# bathroom_fan_power_supply.net
KiCad netlist of a schematic drawn in EAGLE
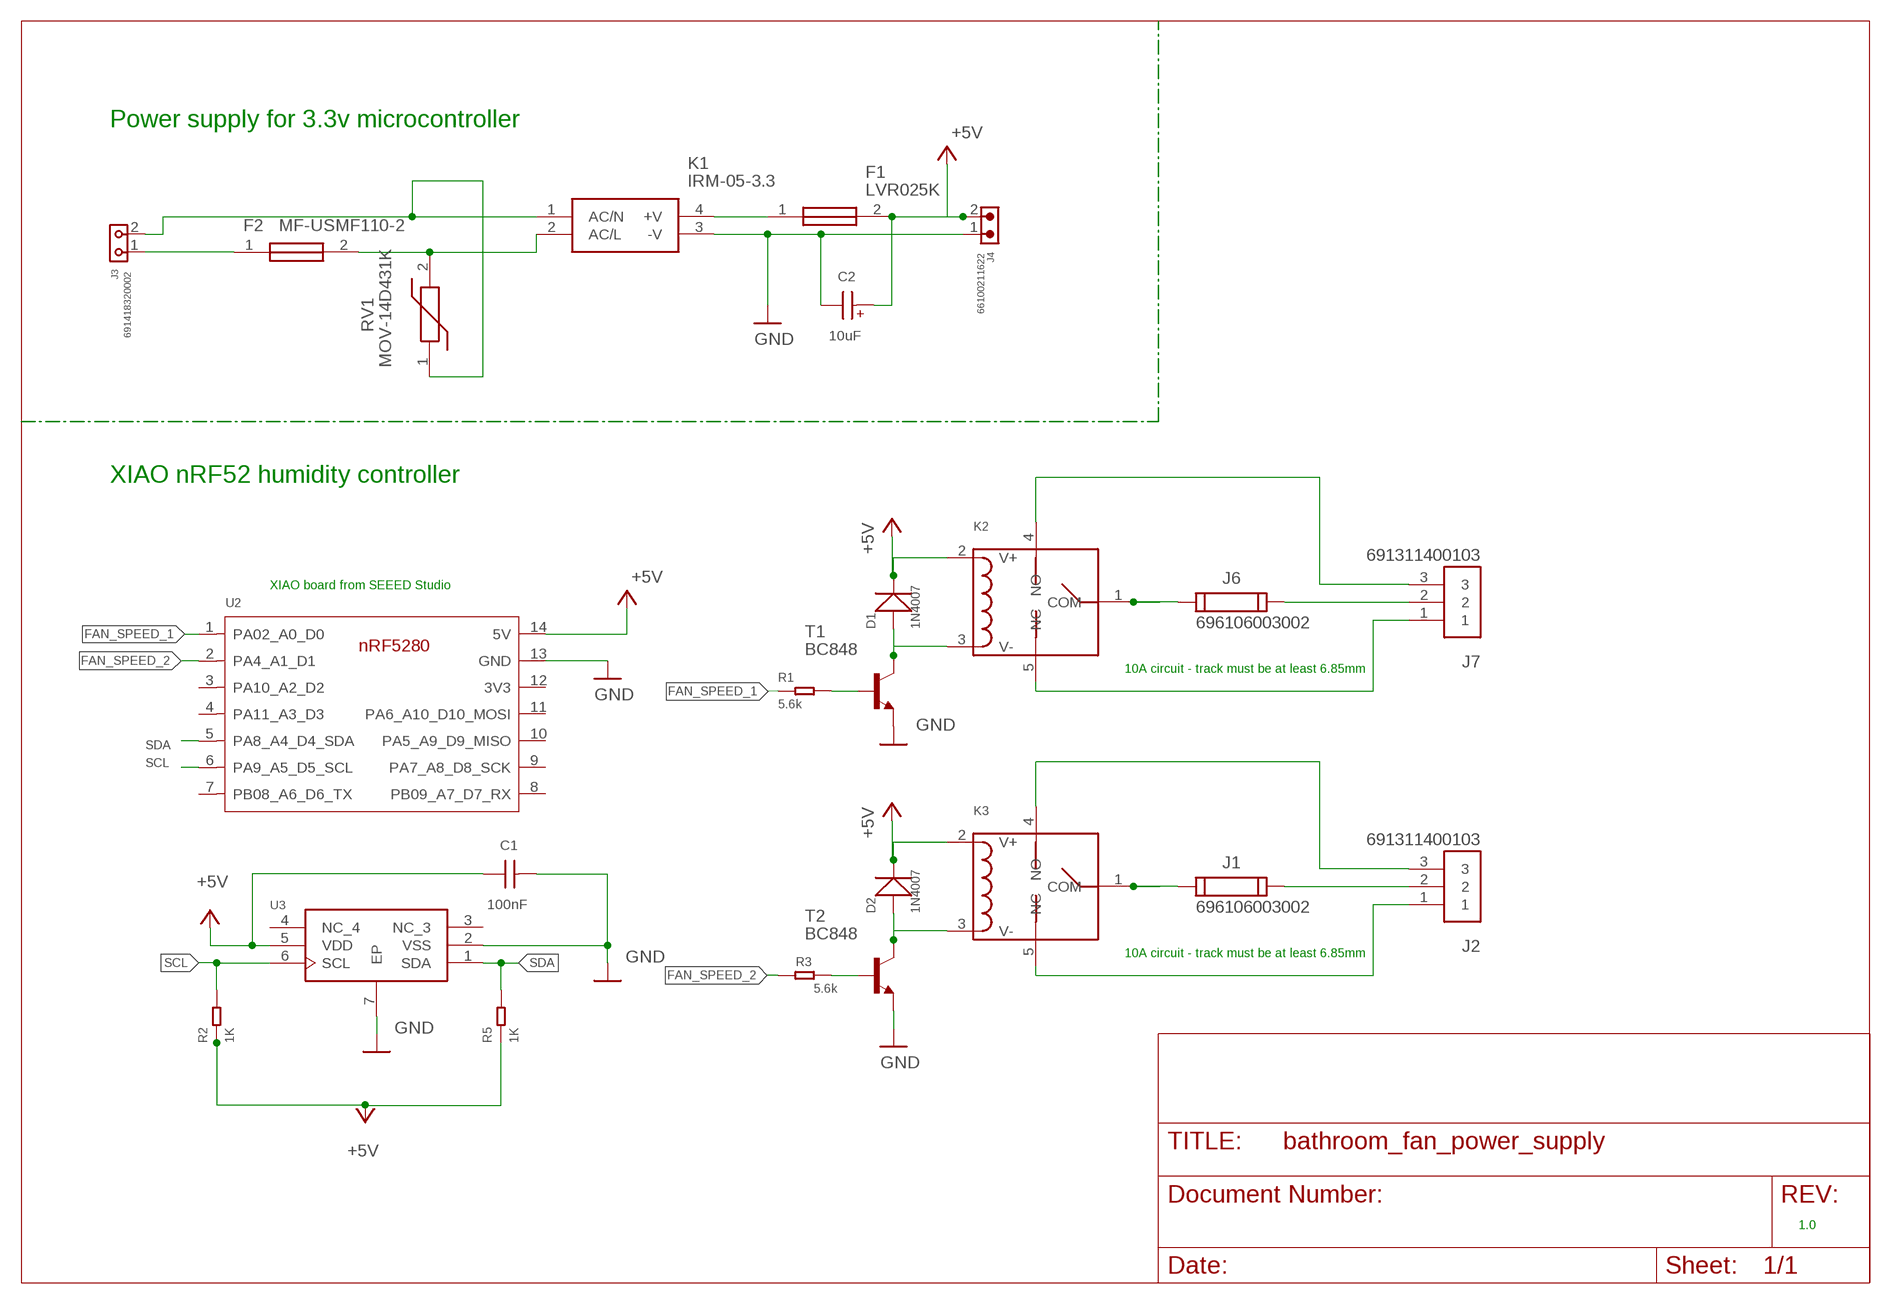
[diagram p0: schematic, sheet 1]

(export (version "E")
  (design (tool "Eeschema 10.0.6"))
  (components
    (comp (ref "C1")
      (value "100nF")
      (footprint "eagle-import:WCAP-CSGP_0805_H0.8_R")
      (libsource (lib "eagle-import") (part "WCAP-CSGP_0805_H0.8_10V(DC)_R_885012207016"))
    )
    (comp (ref "C2")
      (value "10uF")
      (footprint "eagle-import:WCAP-AS5H_4X5.5(DXL)")
      (libsource (lib "eagle-import") (part "WCAP-AS5H_4X5.5_865230340001"))
    )
    (comp (ref "D1")
      (value "1N4007")
      (footprint "eagle-import:DO-214AC")
      (libsource (lib "eagle-import") (part "DIODE-GEN-PURPOSE-1KV-1A(DO-214AC)"))
    )
    (comp (ref "D2")
      (value "1N4007")
      (footprint "eagle-import:DO-214AC")
      (libsource (lib "eagle-import") (part "DIODE-GEN-PURPOSE-1KV-1A(DO-214AC)"))
    )
    (comp (ref "F1")
      (value "LVR025K")
      (footprint "eagle-import:LVR025K")
      (fields (field (name "MOUSER_PART_NUMBER") "650-LVR025K"))
      (libsource (lib "eagle-import") (part "LVR025K"))
    )
    (comp (ref "F2")
      (value "MF-USMF110-2")
      (footprint "eagle-import:FUSC3226X85N")
      (fields (field (name "MOUSER_PART_NUMBER") "652-MF-USMF110-2"))
      (libsource (lib "eagle-import") (part "MF-USMF110-2"))
    )
    (comp (ref "J1")
      (value "696106003002")
      (footprint "eagle-import:696106003002")
      (libsource (lib "eagle-import") (part "696106003002"))
    )
    (comp (ref "J2")
      (value "691311400103")
      (footprint "eagle-import:TERMINALBLOCK_PLUGGABLE-3-7.62MM")
      (fields
        (field (name "DIGIKEY_PART_NO") "732-2824-ND")
        (field (name "MANUFACTURER") "WURTH ELEKTRONIK")
        (field (name "CREATED_BY") "PCBLayout.com")
      )
      (libsource (lib "eagle-import") (part "691311400103"))
    )
    (comp (ref "J3")
      (value "691418320002")
      (footprint "eagle-import:691418320002")
      (libsource (lib "eagle-import") (part "691418320002"))
    )
    (comp (ref "J4")
      (value "66100211622")
      (footprint "eagle-import:66100211622")
      (libsource (lib "eagle-import") (part "66100211622"))
    )
    (comp (ref "J6")
      (value "696106003002")
      (footprint "eagle-import:696106003002")
      (libsource (lib "eagle-import") (part "696106003002"))
    )
    (comp (ref "J7")
      (value "691311400103")
      (footprint "eagle-import:TERMINALBLOCK_PLUGGABLE-3-7.62MM")
      (fields
        (field (name "DIGIKEY_PART_NO") "732-2824-ND")
        (field (name "MANUFACTURER") "WURTH ELEKTRONIK")
        (field (name "CREATED_BY") "PCBLayout.com")
      )
      (libsource (lib "eagle-import") (part "691311400103"))
    )
    (comp (ref "K1")
      (value "IRM-05-3.3")
      (footprint "eagle-import:IRM-05-3.3_1")
      (fields (field (name "MOUSER_PART_NUMBER") "709-IRM05-3.3"))
      (libsource (lib "eagle-import") (part "IRM-05-3.3"))
    )
    (comp (ref "K2")
      (value "HLS8L-DC3V-S-C")
      (footprint "eagle-import:REY5-19.0X15.0X15.0MM")
      (libsource (lib "eagle-import") (part "RELAY-HLS8L-DC5V-S-CHLS8L-DC5V-S-C"))
    )
    (comp (ref "K3")
      (value "HLS8L-DC3V-S-C")
      (footprint "eagle-import:REY5-19.0X15.0X15.0MM")
      (libsource (lib "eagle-import") (part "RELAY-HLS8L-DC5V-S-CHLS8L-DC5V-S-C"))
    )
    (comp (ref "R1")
      (value "5.6k")
      (footprint "eagle-import:R0805")
      (fields (field (name "MPN") "RC0805JR-071KL"))
      (libsource (lib "eagle-import") (part "SMD-RES-5.6K-5%-1/8W(0805)"))
    )
    (comp (ref "R2")
      (value "1K")
      (footprint "eagle-import:R0805")
      (fields (field (name "MPN") "RC0805JR-071KL"))
      (libsource (lib "eagle-import") (part "SMD-RES-5.6K-5%-1/8W(0805)"))
    )
    (comp (ref "R3")
      (value "5.6k")
      (footprint "eagle-import:R0805")
      (fields (field (name "MPN") "RC0805JR-071KL"))
      (libsource (lib "eagle-import") (part "SMD-RES-5.6K-5%-1/8W(0805)"))
    )
    (comp (ref "R5")
      (value "1K")
      (footprint "eagle-import:R0805")
      (fields (field (name "MPN") "RC0805JR-071KL"))
      (libsource (lib "eagle-import") (part "SMD-RES-5.6K-5%-1/8W(0805)"))
    )
    (comp (ref "RV1")
      (value "MOV-14D431K")
      (footprint "eagle-import:MOV-14D(5.2MM-T)")
      (fields (field (name "MOUSER_PART_NUMBER") "652-MOV-14D431K"))
      (libsource (lib "eagle-import") (part "MOV-14D431K"))
    )
    (comp (ref "T1")
      (value "BC848")
      (footprint "eagle-import:SOT23")
      (libsource (lib "eagle-import") (part "BC848"))
    )
    (comp (ref "T2")
      (value "BC848")
      (footprint "eagle-import:SOT23")
      (libsource (lib "eagle-import") (part "BC848"))
    )
    (comp (ref "U2")
      (value "MOUDLE-SEEEDUINO-XIAO")
      (footprint "eagle-import:MOUDLE14P-2.54-21X17.8MM")
      (libsource (lib "eagle-import") (part "MOUDLE-SEEEDUINO-XIAO"))
    )
    (comp (ref "U3")
      (value "SHT21")
      (footprint "eagle-import:6-TDFN")
      (fields
        (field (name "DIGIKEY_PART_NUMBER") "1649-1005-1-ND")
        (field (name "MANUFACTURER") "Sensirion AG")
        (field (name "CREATED_BY") "PCBLayout.com")
      )
      (libsource (lib "eagle-import") (part "SHT21"))
    )
  )
  (nets
    (net (code "1") (name "+5V") (class "Default")
      (node (ref "C1") (pin "1") (pinfunction "1_1") (pintype "passive"))
      (node (ref "C2") (pin "1") (pinfunction "+_1") (pintype "passive"))
      (node (ref "D1") (pin "2") (pinfunction "-_2") (pintype "passive"))
      (node (ref "D2") (pin "2") (pinfunction "-_2") (pintype "passive"))
      (node (ref "F1") (pin "2") (pinfunction "2_2") (pintype "bidirectional"))
      (node (ref "J4") (pin "2") (pinfunction "2_2") (pintype "passive"))
      (node (ref "K2") (pin "2") (pinfunction "V+_2") (pintype "bidirectional"))
      (node (ref "K3") (pin "2") (pinfunction "V+_2") (pintype "bidirectional"))
      (node (ref "R2") (pin "1") (pinfunction "1_1") (pintype "passive"))
      (node (ref "R5") (pin "1") (pinfunction "1_1") (pintype "passive"))
      (node (ref "U2") (pin "14") (pinfunction "5V_14") (pintype "bidirectional"))
      (node (ref "U3") (pin "5") (pinfunction "VDD_5") (pintype "power_in"))
    )
    (net (code "2") (name "FAN_SPEED_1") (class "Default")
      (node (ref "R1") (pin "1") (pinfunction "1_1") (pintype "passive"))
      (node (ref "U2") (pin "1") (pinfunction "PA02_A0_D0_1") (pintype "bidirectional"))
    )
    (net (code "3") (name "FAN_SPEED_2") (class "Default")
      (node (ref "R3") (pin "1") (pinfunction "1_1") (pintype "passive"))
      (node (ref "U2") (pin "2") (pinfunction "PA4_A1_D1_2") (pintype "bidirectional"))
    )
    (net (code "4") (name "GND") (class "Default")
      (node (ref "C1") (pin "2") (pinfunction "2_2") (pintype "passive"))
      (node (ref "C2") (pin "2") (pinfunction "-_2") (pintype "passive"))
      (node (ref "J4") (pin "1") (pinfunction "1_1") (pintype "passive"))
      (node (ref "K1") (pin "3") (pinfunction "-V_3") (pintype "bidirectional"))
      (node (ref "T1") (pin "2") (pinfunction "E_2") (pintype "passive"))
      (node (ref "T2") (pin "2") (pinfunction "E_2") (pintype "passive"))
      (node (ref "U2") (pin "13") (pinfunction "GND_13") (pintype "bidirectional"))
      (node (ref "U3") (pin "2") (pinfunction "VSS_2") (pintype "power_in"))
      (node (ref "U3") (pin "7") (pinfunction "EP_7") (pintype "power_in"))
    )
    (net (code "5") (name "Net-(D1-+)") (class "Default")
      (node (ref "D1") (pin "1") (pinfunction "+_1") (pintype "passive"))
      (node (ref "K2") (pin "3") (pinfunction "V-_3") (pintype "bidirectional"))
      (node (ref "T1") (pin "3") (pinfunction "C_3") (pintype "passive"))
    )
    (net (code "6") (name "Net-(D2-+)") (class "Default")
      (node (ref "D2") (pin "1") (pinfunction "+_1") (pintype "passive"))
      (node (ref "K3") (pin "3") (pinfunction "V-_3") (pintype "bidirectional"))
      (node (ref "T2") (pin "3") (pinfunction "C_3") (pintype "passive"))
    )
    (net (code "7") (name "Net-(F2-Pad1)") (class "Default")
      (node (ref "F2") (pin "1") (pinfunction "1_1") (pintype "bidirectional"))
      (node (ref "J3") (pin "1") (pinfunction "1_1") (pintype "passive"))
    )
    (net (code "8") (name "Net-(J1-Pad2)") (class "Default")
      (node (ref "J1") (pin "2") (pinfunction "2_2") (pintype "passive"))
      (node (ref "J2") (pin "2") (pinfunction "2_2") (pintype "passive"))
    )
    (net (code "9") (name "Net-(J6-Pad2)") (class "Default")
      (node (ref "J6") (pin "2") (pinfunction "2_2") (pintype "passive"))
      (node (ref "J7") (pin "2") (pinfunction "2_2") (pintype "passive"))
    )
    (net (code "10") (name "Net-(K1-+V)") (class "Default")
      (node (ref "F1") (pin "1") (pinfunction "1_1") (pintype "bidirectional"))
      (node (ref "K1") (pin "4") (pinfunction "+V_4") (pintype "bidirectional"))
    )
    (net (code "11") (name "Net-(K1-AC{slash}L)") (class "Default")
      (node (ref "F2") (pin "2") (pinfunction "2_2") (pintype "bidirectional"))
      (node (ref "K1") (pin "2") (pinfunction "AC/L_2") (pintype "bidirectional"))
      (node (ref "RV1") (pin "2") (pinfunction "2_2") (pintype "bidirectional"))
    )
    (net (code "12") (name "Net-(K1-AC{slash}N)") (class "Default")
      (node (ref "J3") (pin "2") (pinfunction "2_2") (pintype "passive"))
      (node (ref "K1") (pin "1") (pinfunction "AC/N_1") (pintype "bidirectional"))
      (node (ref "RV1") (pin "1") (pinfunction "1_1") (pintype "bidirectional"))
    )
    (net (code "13") (name "Net-(K2-COM)") (class "Default")
      (node (ref "J6") (pin "1") (pinfunction "1_1") (pintype "passive"))
      (node (ref "K2") (pin "1") (pinfunction "COM_1") (pintype "bidirectional"))
    )
    (net (code "14") (name "Net-(K2-NC)") (class "Default")
      (node (ref "J7") (pin "1") (pinfunction "1_1") (pintype "passive"))
      (node (ref "K2") (pin "5") (pinfunction "NC_5") (pintype "bidirectional"))
    )
    (net (code "15") (name "Net-(K2-NO)") (class "Default")
      (node (ref "J7") (pin "3") (pinfunction "3_3") (pintype "passive"))
      (node (ref "K2") (pin "4") (pinfunction "NO_4") (pintype "bidirectional"))
    )
    (net (code "16") (name "Net-(K3-COM)") (class "Default")
      (node (ref "J1") (pin "1") (pinfunction "1_1") (pintype "passive"))
      (node (ref "K3") (pin "1") (pinfunction "COM_1") (pintype "bidirectional"))
    )
    (net (code "17") (name "Net-(K3-NC)") (class "Default")
      (node (ref "J2") (pin "1") (pinfunction "1_1") (pintype "passive"))
      (node (ref "K3") (pin "5") (pinfunction "NC_5") (pintype "bidirectional"))
    )
    (net (code "18") (name "Net-(K3-NO)") (class "Default")
      (node (ref "J2") (pin "3") (pinfunction "3_3") (pintype "passive"))
      (node (ref "K3") (pin "4") (pinfunction "NO_4") (pintype "bidirectional"))
    )
    (net (code "19") (name "Net-(T1-B)") (class "Default")
      (node (ref "R1") (pin "2") (pinfunction "2_2") (pintype "passive"))
      (node (ref "T1") (pin "1") (pinfunction "B_1") (pintype "passive"))
    )
    (net (code "20") (name "Net-(T2-B)") (class "Default")
      (node (ref "R3") (pin "2") (pinfunction "2_2") (pintype "passive"))
      (node (ref "T2") (pin "1") (pinfunction "B_1") (pintype "passive"))
    )
    (net (code "21") (name "SCL") (class "Default")
      (node (ref "R2") (pin "2") (pinfunction "2_2") (pintype "passive"))
      (node (ref "U2") (pin "6") (pinfunction "PA9_A5_D5_SCL_6") (pintype "bidirectional"))
      (node (ref "U3") (pin "6") (pinfunction "SCL_6") (pintype "bidirectional"))
    )
    (net (code "22") (name "SDA") (class "Default")
      (node (ref "R5") (pin "2") (pinfunction "2_2") (pintype "passive"))
      (node (ref "U2") (pin "5") (pinfunction "PA8_A4_D4_SDA_5") (pintype "bidirectional"))
      (node (ref "U3") (pin "1") (pinfunction "SDA_1") (pintype "bidirectional"))
    )
    (net (code "23") (name "unconnected-(U2-3V3-Pad12)") (class "Default")
      (node (ref "U2") (pin "12") (pinfunction "3V3_12") (pintype "bidirectional"))
    )
    (net (code "24") (name "unconnected-(U2-PA5_A9_D9_MISO-Pad10)") (class "Default")
      (node (ref "U2") (pin "10") (pinfunction "PA5_A9_D9_MISO_10") (pintype "bidirectional"))
    )
    (net (code "25") (name "unconnected-(U2-PA6_A10_D10_MOSI-Pad11)") (class "Default")
      (node (ref "U2") (pin "11") (pinfunction "PA6_A10_D10_MOSI_11") (pintype "bidirectional"))
    )
    (net (code "26") (name "unconnected-(U2-PA7_A8_D8_SCK-Pad9)") (class "Default")
      (node (ref "U2") (pin "9") (pinfunction "PA7_A8_D8_SCK_9") (pintype "bidirectional"))
    )
    (net (code "27") (name "unconnected-(U2-PA10_A2_D2-Pad3)") (class "Default")
      (node (ref "U2") (pin "3") (pinfunction "PA10_A2_D2_3") (pintype "bidirectional"))
    )
    (net (code "28") (name "unconnected-(U2-PA11_A3_D3-Pad4)") (class "Default")
      (node (ref "U2") (pin "4") (pinfunction "PA11_A3_D3_4") (pintype "bidirectional"))
    )
    (net (code "29") (name "unconnected-(U2-PB08_A6_D6_TX-Pad7)") (class "Default")
      (node (ref "U2") (pin "7") (pinfunction "PB08_A6_D6_TX_7") (pintype "bidirectional"))
    )
    (net (code "30") (name "unconnected-(U2-PB09_A7_D7_RX-Pad8)") (class "Default")
      (node (ref "U2") (pin "8") (pinfunction "PB09_A7_D7_RX_8") (pintype "bidirectional"))
    )
    (net (code "31") (name "unconnected-(U3-NC_3-Pad3)") (class "Default")
      (node (ref "U3") (pin "3") (pinfunction "NC_3_3") (pintype "passive"))
    )
    (net (code "32") (name "unconnected-(U3-NC_4-Pad4)") (class "Default")
      (node (ref "U3") (pin "4") (pinfunction "NC_4_4") (pintype "passive"))
    )
  )
)
